# XICIE_AFE_SMD_revB.net
KiCad netlist of a schematic drawn in EAGLE
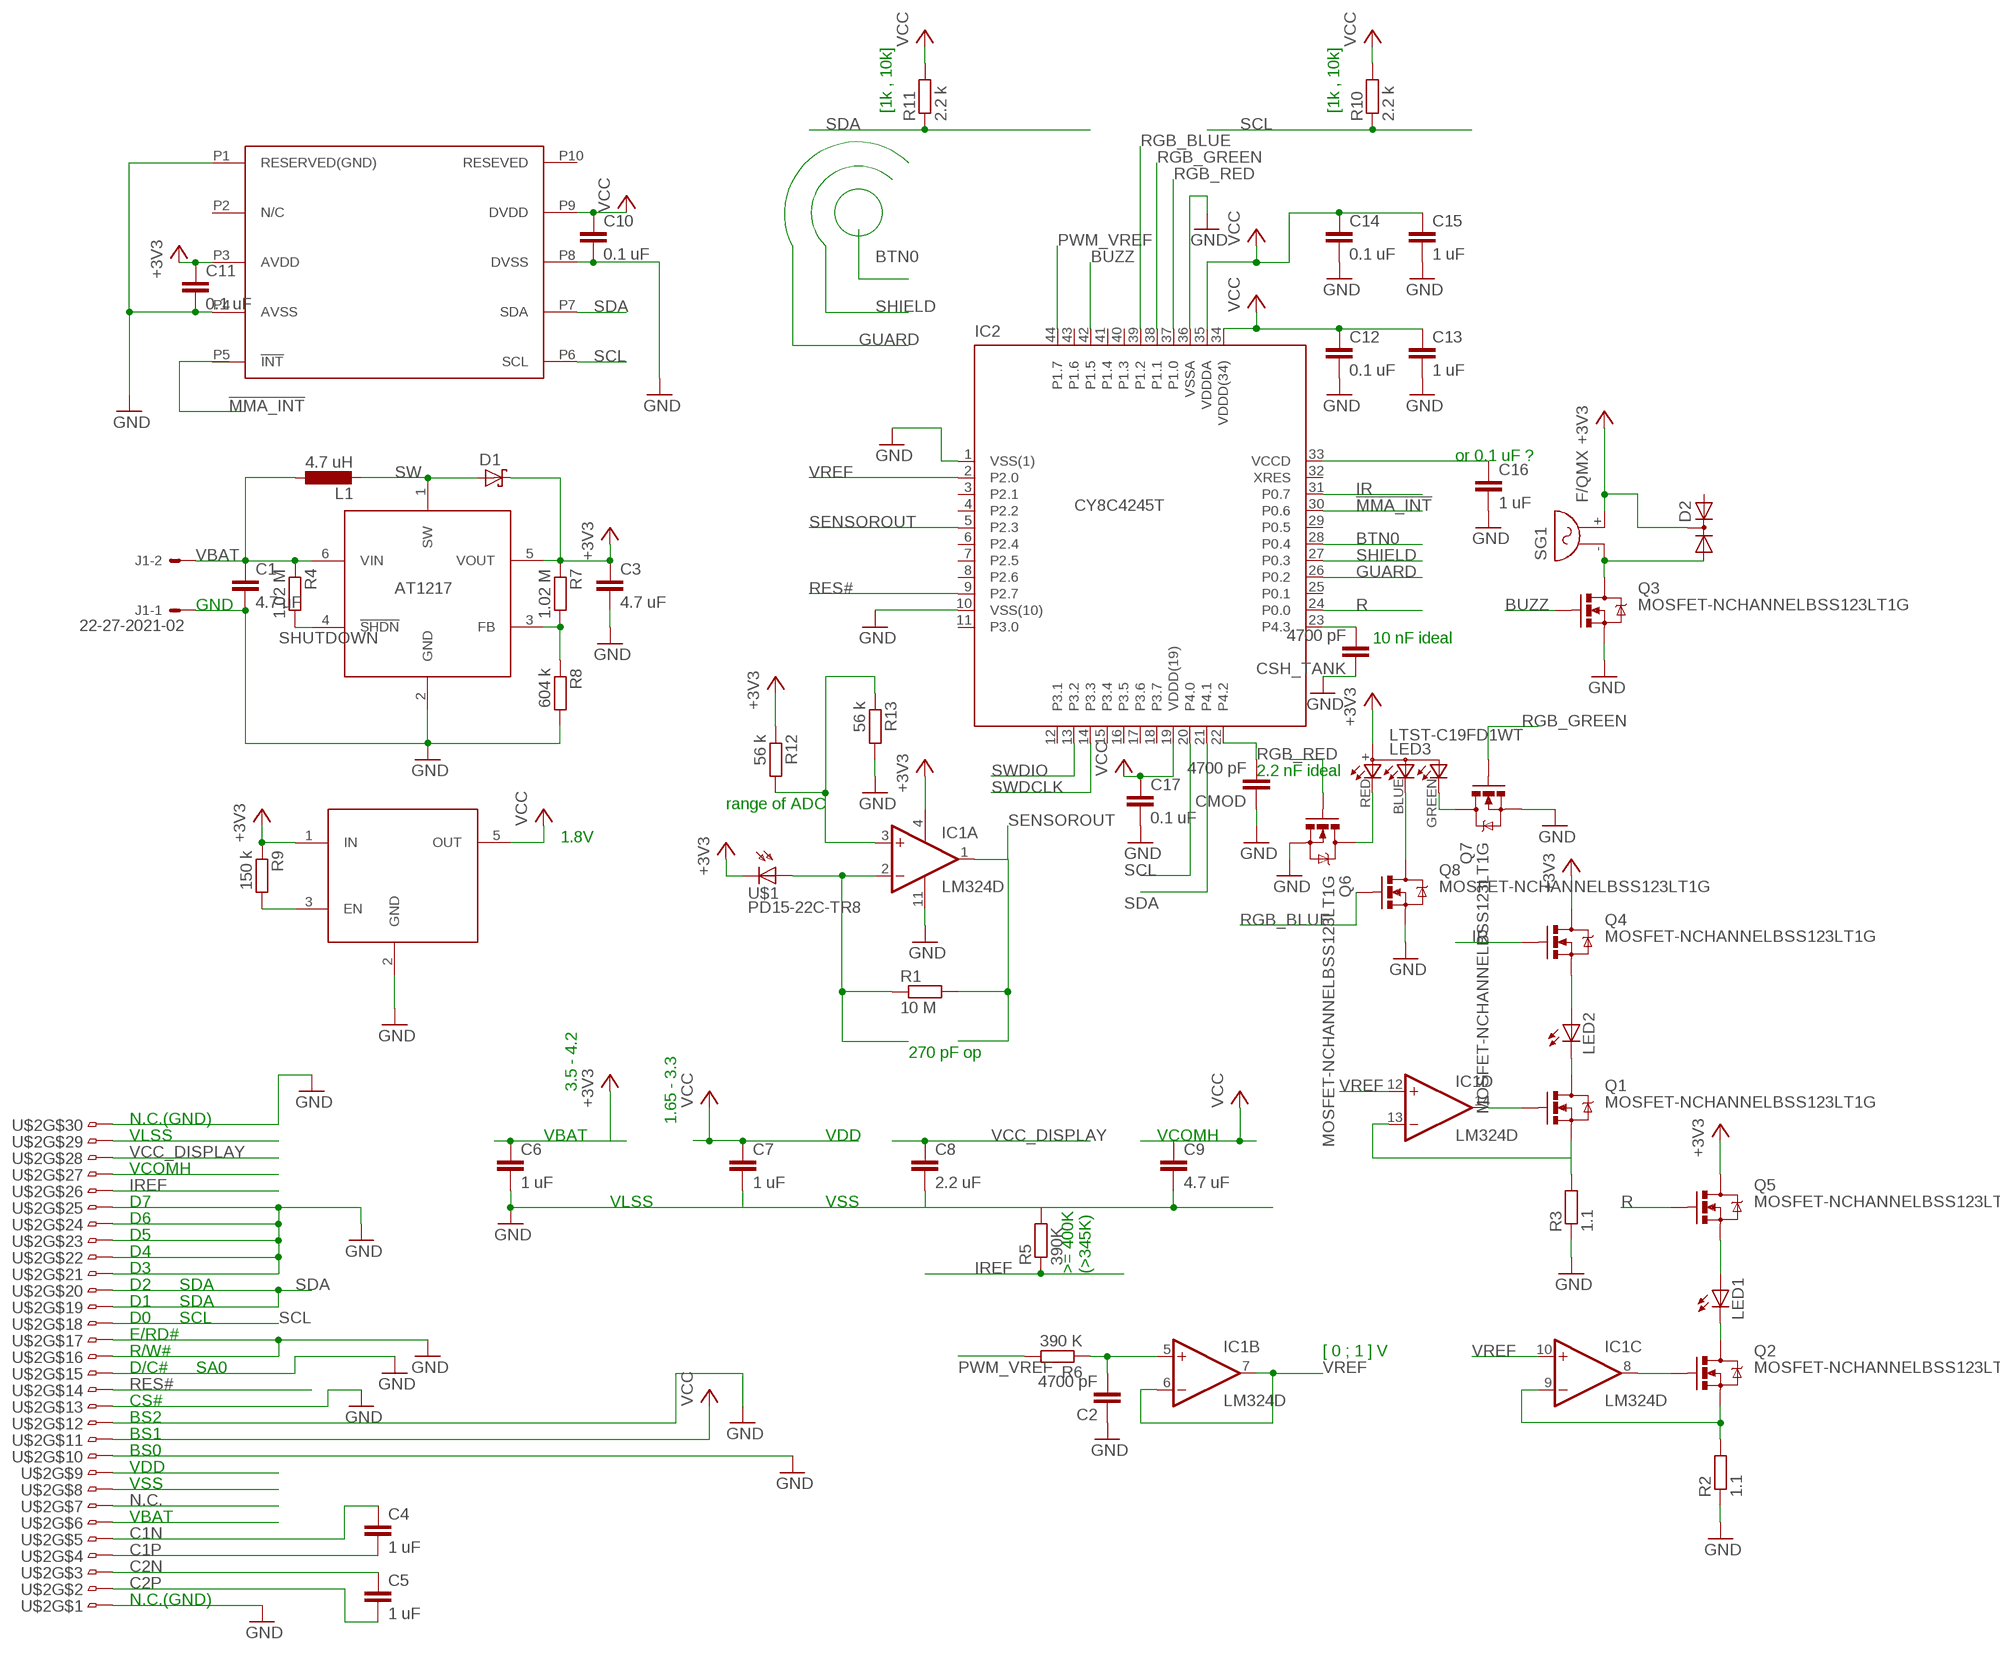
[diagram p0: schematic, sheet 1]

(export (version "E")
  (design (tool "Eeschema 10.0.6"))
  (components
    (comp (ref "C1")
      (value "4.7 uF")
      (footprint "eagle-import:C0603")
      (libsource (lib "eagle-import") (part "C-EUC0603"))
    )
    (comp (ref "C2")
      (value "4700 pF")
      (footprint "eagle-import:C0402")
      (libsource (lib "eagle-import") (part "C-EUC0402"))
    )
    (comp (ref "C3")
      (value "4.7 uF")
      (footprint "eagle-import:C0603")
      (libsource (lib "eagle-import") (part "C-EUC0603"))
    )
    (comp (ref "C4")
      (value "1 uF")
      (footprint "eagle-import:C0402")
      (libsource (lib "eagle-import") (part "C-EUC0402"))
    )
    (comp (ref "C5")
      (value "1 uF")
      (footprint "eagle-import:C0402")
      (libsource (lib "eagle-import") (part "C-EUC0402"))
    )
    (comp (ref "C6")
      (value "1 uF")
      (footprint "eagle-import:C0402")
      (libsource (lib "eagle-import") (part "C-EUC0402"))
    )
    (comp (ref "C7")
      (value "1 uF")
      (footprint "eagle-import:C0402")
      (libsource (lib "eagle-import") (part "C-EUC0402"))
    )
    (comp (ref "C8")
      (value "2.2 uF")
      (footprint "eagle-import:C0603")
      (libsource (lib "eagle-import") (part "C-EUC0603"))
    )
    (comp (ref "C9")
      (value "4.7 uF")
      (footprint "eagle-import:C0603")
      (libsource (lib "eagle-import") (part "C-EUC0603"))
    )
    (comp (ref "C10")
      (value "0.1 uF")
      (footprint "eagle-import:C0402")
      (libsource (lib "eagle-import") (part "C-EUC0402"))
    )
    (comp (ref "C11")
      (value "0.1 uF")
      (footprint "eagle-import:C0402")
      (libsource (lib "eagle-import") (part "C-EUC0402"))
    )
    (comp (ref "C12")
      (value "0.1 uF")
      (footprint "eagle-import:C0402")
      (libsource (lib "eagle-import") (part "C-EUC0402"))
    )
    (comp (ref "C13")
      (value "1 uF")
      (footprint "eagle-import:C0402")
      (libsource (lib "eagle-import") (part "C-EUC0402"))
    )
    (comp (ref "C14")
      (value "0.1 uF")
      (footprint "eagle-import:C0402")
      (libsource (lib "eagle-import") (part "C-EUC0402"))
    )
    (comp (ref "C15")
      (value "1 uF")
      (footprint "eagle-import:C0402")
      (libsource (lib "eagle-import") (part "C-EUC0402"))
    )
    (comp (ref "C16")
      (value "1 uF")
      (footprint "eagle-import:C0402")
      (libsource (lib "eagle-import") (part "C-EUC0402"))
    )
    (comp (ref "C17")
      (value "0.1 uF")
      (footprint "eagle-import:C0402")
      (libsource (lib "eagle-import") (part "C-EUC0402"))
    )
    (comp (ref "CMOD")
      (value "4700 pF")
      (footprint "eagle-import:C0402")
      (libsource (lib "eagle-import") (part "C-EUC0402"))
    )
    (comp (ref "CSH_TANK")
      (value "4700 pF")
      (footprint "eagle-import:C0402")
      (libsource (lib "eagle-import") (part "C-EUC0402"))
    )
    (comp (ref "D1")
      (value "SCHOTTKY-DIODESMD")
      (footprint "eagle-import:SMINI2-F5-B")
      (libsource (lib "eagle-import") (part "SCHOTTKY-DIODESMD"))
    )
    (comp (ref "D2")
      (value "DIODE-2AC|CASOT23")
      (footprint "eagle-import:SOT23")
      (libsource (lib "eagle-import") (part "DIODE-2AC|CASOT23"))
    )
    (comp (ref "IC1")
      (value "LM324D")
      (footprint "eagle-import:SO14")
      (libsource (lib "eagle-import") (part "LM324D"))
    )
    (comp (ref "IC2")
      (value "CY8C4245T")
      (footprint "eagle-import:TQFP44")
      (libsource (lib "eagle-import") (part "CY8C4245T"))
    )
    (comp (ref "IC3")
      (value "AAT1217")
      (footprint "eagle-import:SOT23-6")
      (libsource (lib "eagle-import") (part "AAT1217"))
    )
    (comp (ref "J1")
      (value "22-27-2021-02")
      (footprint "eagle-import:6410-02")
      (libsource (lib "eagle-import") (part "22-?-0227-2021"))
    )
    (comp (ref "L1")
      (value "4.7 uH")
      (footprint "eagle-import:L2518")
      (libsource (lib "eagle-import") (part "L-EU"))
    )
    (comp (ref "LED1")
      (value "LED5MM")
      (footprint "eagle-import:LED5MM")
      (libsource (lib "eagle-import") (part "LED5MM"))
    )
    (comp (ref "LED2")
      (value "LED5MM")
      (footprint "eagle-import:LED5MM")
      (libsource (lib "eagle-import") (part "LED5MM"))
    )
    (comp (ref "LED3")
      (value "LTST-C19FD1WT")
      (footprint "eagle-import:GM1WA55311A")
      (libsource (lib "eagle-import") (part "LTST-C19FD1WT"))
    )
    (comp (ref "Q1")
      (value "MOSFET-NCHANNELBSS123LT1G")
      (footprint "eagle-import:SOT23")
      (libsource (lib "eagle-import") (part "MOSFET-NCHANNELBSS123LT1G"))
    )
    (comp (ref "Q2")
      (value "MOSFET-NCHANNELBSS123LT1G")
      (footprint "eagle-import:SOT23")
      (libsource (lib "eagle-import") (part "MOSFET-NCHANNELBSS123LT1G"))
    )
    (comp (ref "Q3")
      (value "MOSFET-NCHANNELBSS123LT1G")
      (footprint "eagle-import:SOT23")
      (libsource (lib "eagle-import") (part "MOSFET-NCHANNELBSS123LT1G"))
    )
    (comp (ref "Q4")
      (value "MOSFET-NCHANNELBSS123LT1G")
      (footprint "eagle-import:SOT23")
      (libsource (lib "eagle-import") (part "MOSFET-NCHANNELBSS123LT1G"))
    )
    (comp (ref "Q5")
      (value "MOSFET-NCHANNELBSS123LT1G")
      (footprint "eagle-import:SOT23")
      (libsource (lib "eagle-import") (part "MOSFET-NCHANNELBSS123LT1G"))
    )
    (comp (ref "Q6")
      (value "MOSFET-NCHANNELBSS123LT1G")
      (footprint "eagle-import:SOT23")
      (libsource (lib "eagle-import") (part "MOSFET-NCHANNELBSS123LT1G"))
    )
    (comp (ref "Q7")
      (value "MOSFET-NCHANNELBSS123LT1G")
      (footprint "eagle-import:SOT23")
      (libsource (lib "eagle-import") (part "MOSFET-NCHANNELBSS123LT1G"))
    )
    (comp (ref "Q8")
      (value "MOSFET-NCHANNELBSS123LT1G")
      (footprint "eagle-import:SOT23")
      (libsource (lib "eagle-import") (part "MOSFET-NCHANNELBSS123LT1G"))
    )
    (comp (ref "R1")
      (value "10 M")
      (footprint "eagle-import:R0402")
      (libsource (lib "eagle-import") (part "R-EU_R0402"))
    )
    (comp (ref "R2")
      (value "1.1")
      (footprint "eagle-import:R0402")
      (libsource (lib "eagle-import") (part "R-EU_R0402"))
    )
    (comp (ref "R3")
      (value "1.1")
      (footprint "eagle-import:R0402")
      (libsource (lib "eagle-import") (part "R-EU_R0402"))
    )
    (comp (ref "R4")
      (value "1.02 M")
      (footprint "eagle-import:R0805")
      (libsource (lib "eagle-import") (part "R-EU_R0805"))
    )
    (comp (ref "R5")
      (value "390K")
      (footprint "eagle-import:R0603")
      (libsource (lib "eagle-import") (part "resistor_R-EU_R0603"))
    )
    (comp (ref "R6")
      (value "390 K")
      (footprint "eagle-import:R0603")
      (libsource (lib "eagle-import") (part "R-EU_R0603"))
    )
    (comp (ref "R7")
      (value "1.02 M")
      (footprint "eagle-import:R0805")
      (libsource (lib "eagle-import") (part "R-EU_R0805"))
    )
    (comp (ref "R8")
      (value "604 k")
      (footprint "eagle-import:R0603")
      (libsource (lib "eagle-import") (part "R-EU_R0603"))
    )
    (comp (ref "R9")
      (value "150 k")
      (footprint "eagle-import:R0603")
      (libsource (lib "eagle-import") (part "R-EU_R0603"))
    )
    (comp (ref "R10")
      (value "2.2 k")
      (footprint "eagle-import:R0402")
      (libsource (lib "eagle-import") (part "R-EU_R0402"))
    )
    (comp (ref "R11")
      (value "2.2 k")
      (footprint "eagle-import:R0402")
      (libsource (lib "eagle-import") (part "R-EU_R0402"))
    )
    (comp (ref "R12")
      (value "56 k")
      (footprint "eagle-import:R0603")
      (libsource (lib "eagle-import") (part "R-EU_R0603"))
    )
    (comp (ref "R13")
      (value "56 k")
      (footprint "eagle-import:R0603")
      (libsource (lib "eagle-import") (part "R-EU_R0603"))
    )
    (comp (ref "SG1")
      (value "F/QMX")
      (footprint "eagle-import:F_QMX")
      (libsource (lib "eagle-import") (part "F/QMX"))
    )
    (comp (ref "U$1")
      (value "PD15-22C-TR8")
      (footprint "eagle-import:PHOTO_SMD")
      (libsource (lib "eagle-import") (part "PD15-22C-TR8"))
    )
    (comp (ref "U$2")
      (value "ER-OLED0.96")
      (footprint "eagle-import:FLEX0.7X30")
      (libsource (lib "eagle-import") (part "ER-OLED0.96"))
    )
    (comp (ref "U$3")
      (value "AAT3221")
      (footprint "eagle-import:SOT23-5")
      (libsource (lib "eagle-import") (part "AAT3221"))
    )
    (comp (ref "U$4")
      (value "MMA7660FC")
      (footprint "eagle-import:DFN10")
      (libsource (lib "eagle-import") (part "MMA7660FC"))
    )
  )
  (nets
    (net (code "1") (name "+3V3") (class "Default")
      (node (ref "C11") (pin "1") (pinfunction "1_1") (pintype "passive"))
      (node (ref "C3") (pin "1") (pinfunction "1_1") (pintype "passive"))
      (node (ref "C6") (pin "1") (pinfunction "1_1") (pintype "passive"))
      (node (ref "D1") (pin "C") (pinfunction "C_C") (pintype "passive"))
      (node (ref "D2") (pin "3") (pinfunction "C_3") (pintype "passive"))
      (node (ref "IC1") (pin "4") (pinfunction "V+_4") (pintype "power_in"))
      (node (ref "IC3") (pin "5") (pinfunction "VOUT_5") (pintype "bidirectional"))
      (node (ref "LED3") (pin "+") (pinfunction "A_+") (pintype "passive"))
      (node (ref "Q4") (pin "3") (pinfunction "D_3") (pintype "passive"))
      (node (ref "Q5") (pin "3") (pinfunction "D_3") (pintype "passive"))
      (node (ref "R12") (pin "1") (pinfunction "1_1") (pintype "passive"))
      (node (ref "R7") (pin "1") (pinfunction "1_1") (pintype "passive"))
      (node (ref "R9") (pin "1") (pinfunction "1_1") (pintype "passive"))
      (node (ref "SG1") (pin "+") (pinfunction "2_+") (pintype "passive"))
      (node (ref "U$1") (pin "CATHODE1") (pinfunction "C_CATHODE1") (pintype "passive"))
      (node (ref "U$1") (pin "CATHODE2") (pinfunction "C_CATHODE2") (pintype "passive"))
      (node (ref "U$2") (pin "P6") (pinfunction "1_P6") (pintype "passive"))
      (node (ref "U$3") (pin "1") (pinfunction "IN_1") (pintype "bidirectional"))
      (node (ref "U$4") (pin "P3") (pinfunction "AVDD_P3") (pintype "bidirectional"))
    )
    (net (code "2") (name "/BTN0") (class "Default")
      (node (ref "IC2") (pin "28") (pinfunction "P0.4_28") (pintype "bidirectional"))
    )
    (net (code "3") (name "/BUZZ") (class "Default")
      (node (ref "IC2") (pin "42") (pinfunction "P1.5_42") (pintype "bidirectional"))
      (node (ref "Q3") (pin "1") (pinfunction "G_1") (pintype "passive"))
    )
    (net (code "4") (name "/C1N") (class "Default")
      (node (ref "C4") (pin "1") (pinfunction "1_1") (pintype "passive"))
      (node (ref "U$2") (pin "P5") (pinfunction "1_P5") (pintype "passive"))
    )
    (net (code "5") (name "/C1P") (class "Default")
      (node (ref "C4") (pin "2") (pinfunction "2_2") (pintype "passive"))
      (node (ref "U$2") (pin "P4") (pinfunction "1_P4") (pintype "passive"))
    )
    (net (code "6") (name "/C2N") (class "Default")
      (node (ref "C5") (pin "1") (pinfunction "1_1") (pintype "passive"))
      (node (ref "U$2") (pin "P3") (pinfunction "1_P3") (pintype "passive"))
    )
    (net (code "7") (name "/C2P") (class "Default")
      (node (ref "C5") (pin "2") (pinfunction "2_2") (pintype "passive"))
      (node (ref "U$2") (pin "P2") (pinfunction "1_P2") (pintype "passive"))
    )
    (net (code "8") (name "/GUARD") (class "Default")
      (node (ref "IC2") (pin "26") (pinfunction "P0.2_26") (pintype "input"))
    )
    (net (code "9") (name "/IR") (class "Default")
      (node (ref "IC2") (pin "31") (pinfunction "P0.7_31") (pintype "bidirectional"))
      (node (ref "Q4") (pin "1") (pinfunction "G_1") (pintype "passive"))
    )
    (net (code "10") (name "/IREF") (class "Default")
      (node (ref "R5") (pin "1") (pinfunction "1_1") (pintype "passive"))
      (node (ref "U$2") (pin "P26") (pinfunction "1_P26") (pintype "passive"))
    )
    (net (code "11") (name "/N.C.") (class "Default")
      (node (ref "U$2") (pin "P7") (pinfunction "1_P7") (pintype "passive"))
    )
    (net (code "12") (name "/P2.2") (class "Default")
      (node (ref "IC2") (pin "4") (pinfunction "P2.2_4") (pintype "power_in"))
    )
    (net (code "13") (name "/P2.6") (class "Default")
      (node (ref "IC2") (pin "8") (pinfunction "P2.6_8") (pintype "power_in"))
    )
    (net (code "14") (name "/P3.6") (class "Default")
      (node (ref "IC2") (pin "17") (pinfunction "P3.6_17") (pintype "power_in"))
    )
    (net (code "15") (name "/PWM_VREF") (class "Default")
      (node (ref "IC2") (pin "44") (pinfunction "P1.7_44") (pintype "bidirectional"))
      (node (ref "R6") (pin "2") (pinfunction "2_2") (pintype "passive"))
    )
    (net (code "16") (name "/R") (class "Default")
      (node (ref "IC2") (pin "24") (pinfunction "P0.0_24") (pintype "bidirectional"))
      (node (ref "Q5") (pin "1") (pinfunction "G_1") (pintype "passive"))
    )
    (net (code "17") (name "/RES#") (class "Default")
      (node (ref "IC2") (pin "9") (pinfunction "P2.7_9") (pintype "bidirectional"))
      (node (ref "U$2") (pin "P14") (pinfunction "1_P14") (pintype "passive"))
    )
    (net (code "18") (name "/RGB_BLUE") (class "Default")
      (node (ref "IC2") (pin "39") (pinfunction "P1.2_39") (pintype "power_in"))
      (node (ref "Q8") (pin "1") (pinfunction "G_1") (pintype "passive"))
    )
    (net (code "19") (name "/RGB_GREEN") (class "Default")
      (node (ref "IC2") (pin "38") (pinfunction "P1.1_38") (pintype "bidirectional"))
      (node (ref "Q7") (pin "1") (pinfunction "G_1") (pintype "passive"))
    )
    (net (code "20") (name "/RGB_RED") (class "Default")
      (node (ref "IC2") (pin "37") (pinfunction "P1.0_37") (pintype "bidirectional"))
      (node (ref "Q6") (pin "1") (pinfunction "G_1") (pintype "passive"))
    )
    (net (code "21") (name "/SCL") (class "Default")
      (node (ref "IC2") (pin "20") (pinfunction "P4.0_20") (pintype "bidirectional"))
      (node (ref "R10") (pin "1") (pinfunction "1_1") (pintype "passive"))
      (node (ref "U$2") (pin "P18") (pinfunction "1_P18") (pintype "passive"))
      (node (ref "U$4") (pin "P6") (pinfunction "SCL_P6") (pintype "bidirectional"))
    )
    (net (code "22") (name "/SDA") (class "Default")
      (node (ref "IC2") (pin "21") (pinfunction "P4.1_21") (pintype "bidirectional"))
      (node (ref "R11") (pin "1") (pinfunction "1_1") (pintype "passive"))
      (node (ref "U$2") (pin "P19") (pinfunction "1_P19") (pintype "passive"))
      (node (ref "U$2") (pin "P20") (pinfunction "1_P20") (pintype "passive"))
      (node (ref "U$4") (pin "P7") (pinfunction "SDA_P7") (pintype "bidirectional"))
    )
    (net (code "23") (name "/SENSOROUT") (class "Default")
      (node (ref "IC1") (pin "1") (pinfunction "OUT_1") (pintype "output"))
      (node (ref "IC2") (pin "5") (pinfunction "P2.3_5") (pintype "bidirectional"))
      (node (ref "R1") (pin "2") (pinfunction "2_2") (pintype "passive"))
    )
    (net (code "24") (name "/SHIELD") (class "Default")
      (node (ref "IC2") (pin "27") (pinfunction "P0.3_27") (pintype "bidirectional"))
    )
    (net (code "25") (name "/SHUTDOWN") (class "Default")
      (node (ref "IC3") (pin "4") (pinfunction "~{SHDN}_4") (pintype "bidirectional"))
      (node (ref "R4") (pin "2") (pinfunction "2_2") (pintype "passive"))
    )
    (net (code "26") (name "/SW") (class "Default")
      (node (ref "D1") (pin "A") (pinfunction "A_A") (pintype "passive"))
      (node (ref "IC3") (pin "1") (pinfunction "SW_1") (pintype "bidirectional"))
      (node (ref "L1") (pin "2") (pinfunction "2_2") (pintype "passive"))
    )
    (net (code "27") (name "/SWDCLK") (class "Default")
      (node (ref "IC2") (pin "14") (pinfunction "P3.3_14") (pintype "bidirectional"))
    )
    (net (code "28") (name "/SWDIO") (class "Default")
      (node (ref "IC2") (pin "13") (pinfunction "P3.2_13") (pintype "bidirectional"))
    )
    (net (code "29") (name "/VBAT") (class "Default")
      (node (ref "C1") (pin "1") (pinfunction "1_1") (pintype "passive"))
      (node (ref "IC3") (pin "6") (pinfunction "VIN_6") (pintype "bidirectional"))
      (node (ref "J1") (pin "2") (pinfunction "S_2") (pintype "passive"))
      (node (ref "L1") (pin "1") (pinfunction "1_1") (pintype "passive"))
      (node (ref "R4") (pin "1") (pinfunction "1_1") (pintype "passive"))
    )
    (net (code "30") (name "/VCC_DISPLAY") (class "Default")
      (node (ref "C8") (pin "1") (pinfunction "1_1") (pintype "passive"))
      (node (ref "U$2") (pin "P28") (pinfunction "1_P28") (pintype "passive"))
    )
    (net (code "31") (name "/VREF") (class "Default")
      (node (ref "IC1") (pin "10") (pinfunction "+IN_10") (pintype "input"))
      (node (ref "IC1") (pin "12") (pinfunction "+IN_12") (pintype "input"))
      (node (ref "IC1") (pin "6") (pinfunction "-IN_6") (pintype "input"))
      (node (ref "IC1") (pin "7") (pinfunction "OUT_7") (pintype "output"))
      (node (ref "IC2") (pin "2") (pinfunction "P2.0_2") (pintype "bidirectional"))
    )
    (net (code "32") (name "/~{MMA_INT}") (class "Default")
      (node (ref "IC2") (pin "30") (pinfunction "P0.6_30") (pintype "power_in"))
    )
    (net (code "33") (name "GND") (class "Default")
      (node (ref "C1") (pin "2") (pinfunction "2_2") (pintype "passive"))
      (node (ref "C10") (pin "2") (pinfunction "2_2") (pintype "passive"))
      (node (ref "C11") (pin "2") (pinfunction "2_2") (pintype "passive"))
      (node (ref "C12") (pin "2") (pinfunction "2_2") (pintype "passive"))
      (node (ref "C13") (pin "2") (pinfunction "2_2") (pintype "passive"))
      (node (ref "C14") (pin "2") (pinfunction "2_2") (pintype "passive"))
      (node (ref "C15") (pin "2") (pinfunction "2_2") (pintype "passive"))
      (node (ref "C16") (pin "2") (pinfunction "2_2") (pintype "passive"))
      (node (ref "C17") (pin "2") (pinfunction "2_2") (pintype "passive"))
      (node (ref "C2") (pin "1") (pinfunction "1_1") (pintype "passive"))
      (node (ref "C3") (pin "2") (pinfunction "2_2") (pintype "passive"))
      (node (ref "C6") (pin "2") (pinfunction "2_2") (pintype "passive"))
      (node (ref "C7") (pin "2") (pinfunction "2_2") (pintype "passive"))
      (node (ref "C8") (pin "2") (pinfunction "2_2") (pintype "passive"))
      (node (ref "C9") (pin "2") (pinfunction "2_2") (pintype "passive"))
      (node (ref "CMOD") (pin "1") (pinfunction "1_1") (pintype "passive"))
      (node (ref "CSH_TANK") (pin "1") (pinfunction "1_1") (pintype "passive"))
      (node (ref "IC1") (pin "11") (pinfunction "V-_11") (pintype "power_in"))
      (node (ref "IC2") (pin "1") (pinfunction "VSS(1)_1") (pintype "bidirectional"))
      (node (ref "IC2") (pin "10") (pinfunction "VSS(10)_10") (pintype "bidirectional"))
      (node (ref "IC2") (pin "36") (pinfunction "VSSA_36") (pintype "bidirectional"))
      (node (ref "IC3") (pin "2") (pinfunction "GND_2") (pintype "bidirectional"))
      (node (ref "J1") (pin "1") (pinfunction "S_1") (pintype "passive"))
      (node (ref "Q3") (pin "2") (pinfunction "S_2") (pintype "passive"))
      (node (ref "Q6") (pin "2") (pinfunction "S_2") (pintype "passive"))
      (node (ref "Q7") (pin "2") (pinfunction "S_2") (pintype "passive"))
      (node (ref "Q8") (pin "2") (pinfunction "S_2") (pintype "passive"))
      (node (ref "R13") (pin "2") (pinfunction "2_2") (pintype "passive"))
      (node (ref "R2") (pin "1") (pinfunction "1_1") (pintype "passive"))
      (node (ref "R3") (pin "1") (pinfunction "1_1") (pintype "passive"))
      (node (ref "R5") (pin "2") (pinfunction "2_2") (pintype "passive"))
      (node (ref "R8") (pin "2") (pinfunction "2_2") (pintype "passive"))
      (node (ref "U$2") (pin "P1") (pinfunction "1_P1") (pintype "passive"))
      (node (ref "U$2") (pin "P10") (pinfunction "1_P10") (pintype "passive"))
      (node (ref "U$2") (pin "P12") (pinfunction "1_P12") (pintype "passive"))
      (node (ref "U$2") (pin "P13") (pinfunction "1_P13") (pintype "passive"))
      (node (ref "U$2") (pin "P15") (pinfunction "1_P15") (pintype "passive"))
      (node (ref "U$2") (pin "P16") (pinfunction "1_P16") (pintype "passive"))
      (node (ref "U$2") (pin "P17") (pinfunction "1_P17") (pintype "passive"))
      (node (ref "U$2") (pin "P21") (pinfunction "1_P21") (pintype "passive"))
      (node (ref "U$2") (pin "P22") (pinfunction "1_P22") (pintype "passive"))
      (node (ref "U$2") (pin "P23") (pinfunction "1_P23") (pintype "passive"))
      (node (ref "U$2") (pin "P24") (pinfunction "1_P24") (pintype "passive"))
      (node (ref "U$2") (pin "P25") (pinfunction "1_P25") (pintype "passive"))
      (node (ref "U$2") (pin "P29") (pinfunction "1_P29") (pintype "passive"))
      (node (ref "U$2") (pin "P30") (pinfunction "1_P30") (pintype "passive"))
      (node (ref "U$2") (pin "P8") (pinfunction "1_P8") (pintype "passive"))
      (node (ref "U$3") (pin "2") (pinfunction "GND_2") (pintype "bidirectional"))
      (node (ref "U$4") (pin "P1") (pinfunction "RESERVED(GND)_P1") (pintype "bidirectional"))
      (node (ref "U$4") (pin "P4") (pinfunction "AVSS_P4") (pintype "bidirectional"))
      (node (ref "U$4") (pin "P8") (pinfunction "DVSS_P8") (pintype "bidirectional"))
    )
    (net (code "34") (name "Net-(D2-A1)") (class "Default")
      (node (ref "D2") (pin "1") (pinfunction "A1_1") (pintype "passive"))
      (node (ref "Q3") (pin "3") (pinfunction "D_3") (pintype "passive"))
      (node (ref "SG1") (pin "-") (pinfunction "1_-") (pintype "passive"))
    )
    (net (code "35") (name "Net-(IC1A-+IN)") (class "Default")
      (node (ref "IC1") (pin "3") (pinfunction "+IN_3") (pintype "input"))
      (node (ref "R12") (pin "2") (pinfunction "2_2") (pintype "passive"))
      (node (ref "R13") (pin "1") (pinfunction "1_1") (pintype "passive"))
    )
    (net (code "36") (name "Net-(IC1A--IN)") (class "Default")
      (node (ref "IC1") (pin "2") (pinfunction "-IN_2") (pintype "input"))
      (node (ref "R1") (pin "1") (pinfunction "1_1") (pintype "passive"))
      (node (ref "U$1") (pin "ANODE1") (pinfunction "A_ANODE1") (pintype "passive"))
      (node (ref "U$1") (pin "ANODE2") (pinfunction "A_ANODE2") (pintype "passive"))
    )
    (net (code "37") (name "Net-(IC1B-+IN)") (class "Default")
      (node (ref "C2") (pin "2") (pinfunction "2_2") (pintype "passive"))
      (node (ref "IC1") (pin "5") (pinfunction "+IN_5") (pintype "input"))
      (node (ref "R6") (pin "1") (pinfunction "1_1") (pintype "passive"))
    )
    (net (code "38") (name "Net-(IC1C--IN)") (class "Default")
      (node (ref "IC1") (pin "9") (pinfunction "-IN_9") (pintype "input"))
      (node (ref "Q2") (pin "2") (pinfunction "S_2") (pintype "passive"))
      (node (ref "R2") (pin "2") (pinfunction "2_2") (pintype "passive"))
    )
    (net (code "39") (name "Net-(IC1C-OUT)") (class "Default")
      (node (ref "IC1") (pin "8") (pinfunction "OUT_8") (pintype "output"))
      (node (ref "Q2") (pin "1") (pinfunction "G_1") (pintype "passive"))
    )
    (net (code "40") (name "Net-(IC1D--IN)") (class "Default")
      (node (ref "IC1") (pin "13") (pinfunction "-IN_13") (pintype "input"))
      (node (ref "Q1") (pin "2") (pinfunction "S_2") (pintype "passive"))
      (node (ref "R3") (pin "2") (pinfunction "2_2") (pintype "passive"))
    )
    (net (code "41") (name "Net-(IC1D-OUT)") (class "Default")
      (node (ref "IC1") (pin "14") (pinfunction "OUT_14") (pintype "output"))
      (node (ref "Q1") (pin "1") (pinfunction "G_1") (pintype "passive"))
    )
    (net (code "42") (name "Net-(IC2-P4.2)") (class "Default")
      (node (ref "CMOD") (pin "2") (pinfunction "2_2") (pintype "passive"))
      (node (ref "IC2") (pin "22") (pinfunction "P4.2_22") (pintype "bidirectional"))
    )
    (net (code "43") (name "Net-(IC2-P4.3)") (class "Default")
      (node (ref "CSH_TANK") (pin "2") (pinfunction "2_2") (pintype "passive"))
      (node (ref "IC2") (pin "23") (pinfunction "P4.3_23") (pintype "bidirectional"))
    )
    (net (code "44") (name "Net-(IC2-VCCD)") (class "Default")
      (node (ref "C16") (pin "1") (pinfunction "1_1") (pintype "passive"))
      (node (ref "IC2") (pin "33") (pinfunction "VCCD_33") (pintype "bidirectional"))
    )
    (net (code "45") (name "Net-(IC3-FB)") (class "Default")
      (node (ref "IC3") (pin "3") (pinfunction "FB_3") (pintype "bidirectional"))
      (node (ref "R7") (pin "2") (pinfunction "2_2") (pintype "passive"))
      (node (ref "R8") (pin "1") (pinfunction "1_1") (pintype "passive"))
    )
    (net (code "46") (name "Net-(LED1-C)") (class "Default")
      (node (ref "LED1") (pin "K") (pinfunction "C_K") (pintype "passive"))
      (node (ref "Q2") (pin "3") (pinfunction "D_3") (pintype "passive"))
    )
    (net (code "47") (name "Net-(LED2-C)") (class "Default")
      (node (ref "LED2") (pin "K") (pinfunction "C_K") (pintype "passive"))
      (node (ref "Q1") (pin "3") (pinfunction "D_3") (pintype "passive"))
    )
    (net (code "48") (name "Net-(LED3-CBLUE)") (class "Default")
      (node (ref "LED3") (pin "BLUE") (pinfunction "CBLUE_BLUE") (pintype "passive"))
      (node (ref "Q8") (pin "3") (pinfunction "D_3") (pintype "passive"))
    )
    (net (code "49") (name "Net-(LED3-CGREEN)") (class "Default")
      (node (ref "LED3") (pin "GREEN") (pinfunction "CGREEN_GREEN") (pintype "passive"))
      (node (ref "Q7") (pin "3") (pinfunction "D_3") (pintype "passive"))
    )
    (net (code "50") (name "Net-(LED3-CRED)") (class "Default")
      (node (ref "LED3") (pin "RED") (pinfunction "CRED_RED") (pintype "passive"))
      (node (ref "Q6") (pin "3") (pinfunction "D_3") (pintype "passive"))
    )
    (net (code "51") (name "Net-(Q4-S)") (class "Default")
      (node (ref "LED2") (pin "A") (pinfunction "A_A") (pintype "passive"))
      (node (ref "Q4") (pin "2") (pinfunction "S_2") (pintype "passive"))
    )
    (net (code "52") (name "Net-(Q5-S)") (class "Default")
      (node (ref "LED1") (pin "A") (pinfunction "A_A") (pintype "passive"))
      (node (ref "Q5") (pin "2") (pinfunction "S_2") (pintype "passive"))
    )
    (net (code "53") (name "Net-(U$3-EN)") (class "Default")
      (node (ref "R9") (pin "2") (pinfunction "2_2") (pintype "passive"))
      (node (ref "U$3") (pin "3") (pinfunction "EN_3") (pintype "bidirectional"))
    )
    (net (code "54") (name "VCC") (class "Default")
      (node (ref "C10") (pin "1") (pinfunction "1_1") (pintype "passive"))
      (node (ref "C12") (pin "1") (pinfunction "1_1") (pintype "passive"))
      (node (ref "C13") (pin "1") (pinfunction "1_1") (pintype "passive"))
      (node (ref "C14") (pin "1") (pinfunction "1_1") (pintype "passive"))
      (node (ref "C15") (pin "1") (pinfunction "1_1") (pintype "passive"))
      (node (ref "C17") (pin "1") (pinfunction "1_1") (pintype "passive"))
      (node (ref "C7") (pin "1") (pinfunction "1_1") (pintype "passive"))
      (node (ref "C9") (pin "1") (pinfunction "1_1") (pintype "passive"))
      (node (ref "IC2") (pin "19") (pinfunction "VDDD(19)_19") (pintype "bidirectional"))
      (node (ref "IC2") (pin "34") (pinfunction "VDDD(34)_34") (pintype "bidirectional"))
      (node (ref "IC2") (pin "35") (pinfunction "VDDDA_35") (pintype "bidirectional"))
      (node (ref "R10") (pin "2") (pinfunction "2_2") (pintype "passive"))
      (node (ref "R11") (pin "2") (pinfunction "2_2") (pintype "passive"))
      (node (ref "U$2") (pin "P11") (pinfunction "1_P11") (pintype "passive"))
      (node (ref "U$2") (pin "P27") (pinfunction "1_P27") (pintype "passive"))
      (node (ref "U$2") (pin "P9") (pinfunction "1_P9") (pintype "passive"))
      (node (ref "U$3") (pin "5") (pinfunction "OUT_5") (pintype "bidirectional"))
      (node (ref "U$4") (pin "P9") (pinfunction "DVDD_P9") (pintype "bidirectional"))
    )
    (net (code "55") (name "unconnected-(D2-A2-Pad2)") (class "Default")
      (node (ref "D2") (pin "2") (pinfunction "A2_2") (pintype "passive"))
    )
    (net (code "56") (name "unconnected-(IC2-P0.1-Pad25)") (class "Default")
      (node (ref "IC2") (pin "25") (pinfunction "P0.1_25") (pintype "bidirectional"))
    )
    (net (code "57") (name "unconnected-(IC2-P0.5-Pad29)") (class "Default")
      (node (ref "IC2") (pin "29") (pinfunction "P0.5_29") (pintype "bidirectional"))
    )
    (net (code "58") (name "unconnected-(IC2-P1.3-Pad40)") (class "Default")
      (node (ref "IC2") (pin "40") (pinfunction "P1.3_40") (pintype "bidirectional"))
    )
    (net (code "59") (name "unconnected-(IC2-P1.4-Pad41)") (class "Default")
      (node (ref "IC2") (pin "41") (pinfunction "P1.4_41") (pintype "bidirectional"))
    )
    (net (code "60") (name "unconnected-(IC2-P1.6-Pad43)") (class "Default")
      (node (ref "IC2") (pin "43") (pinfunction "P1.6_43") (pintype "bidirectional"))
    )
    (net (code "61") (name "unconnected-(IC2-P2.1-Pad3)") (class "Default")
      (node (ref "IC2") (pin "3") (pinfunction "P2.1_3") (pintype "bidirectional"))
    )
    (net (code "62") (name "unconnected-(IC2-P2.4-Pad6)") (class "Default")
      (node (ref "IC2") (pin "6") (pinfunction "P2.4_6") (pintype "bidirectional"))
    )
    (net (code "63") (name "unconnected-(IC2-P2.5-Pad7)") (class "Default")
      (node (ref "IC2") (pin "7") (pinfunction "P2.5_7") (pintype "bidirectional"))
    )
    (net (code "64") (name "unconnected-(IC2-P3.0-Pad11)") (class "Default")
      (node (ref "IC2") (pin "11") (pinfunction "P3.0_11") (pintype "bidirectional"))
    )
    (net (code "65") (name "unconnected-(IC2-P3.1-Pad12)") (class "Default")
      (node (ref "IC2") (pin "12") (pinfunction "P3.1_12") (pintype "bidirectional"))
    )
    (net (code "66") (name "unconnected-(IC2-P3.4-Pad15)") (class "Default")
      (node (ref "IC2") (pin "15") (pinfunction "P3.4_15") (pintype "bidirectional"))
    )
    (net (code "67") (name "unconnected-(IC2-P3.5-Pad16)") (class "Default")
      (node (ref "IC2") (pin "16") (pinfunction "P3.5_16") (pintype "bidirectional"))
    )
    (net (code "68") (name "unconnected-(IC2-P3.7-Pad18)") (class "Default")
      (node (ref "IC2") (pin "18") (pinfunction "P3.7_18") (pintype "bidirectional"))
    )
    (net (code "69") (name "unconnected-(IC2-XRES-Pad32)") (class "Default")
      (node (ref "IC2") (pin "32") (pinfunction "XRES_32") (pintype "bidirectional"))
    )
    (net (code "70") (name "unconnected-(U$4-N{slash}C-PadP2)") (class "Default")
      (node (ref "U$4") (pin "P2") (pinfunction "N/C_P2") (pintype "bidirectional"))
    )
    (net (code "71") (name "unconnected-(U$4-RESEVED-PadP10)") (class "Default")
      (node (ref "U$4") (pin "P10") (pinfunction "RESEVED_P10") (pintype "bidirectional"))
    )
    (net (code "72") (name "unconnected-(U$4-~{INT}-PadP5)") (class "Default")
      (node (ref "U$4") (pin "P5") (pinfunction "~{INT}_P5") (pintype "bidirectional"))
    )
  )
)
